# 27_-_PWR_1V375_OPT_3V3_OPT.net
KiCad netlist of a schematic drawn in Altium Designer
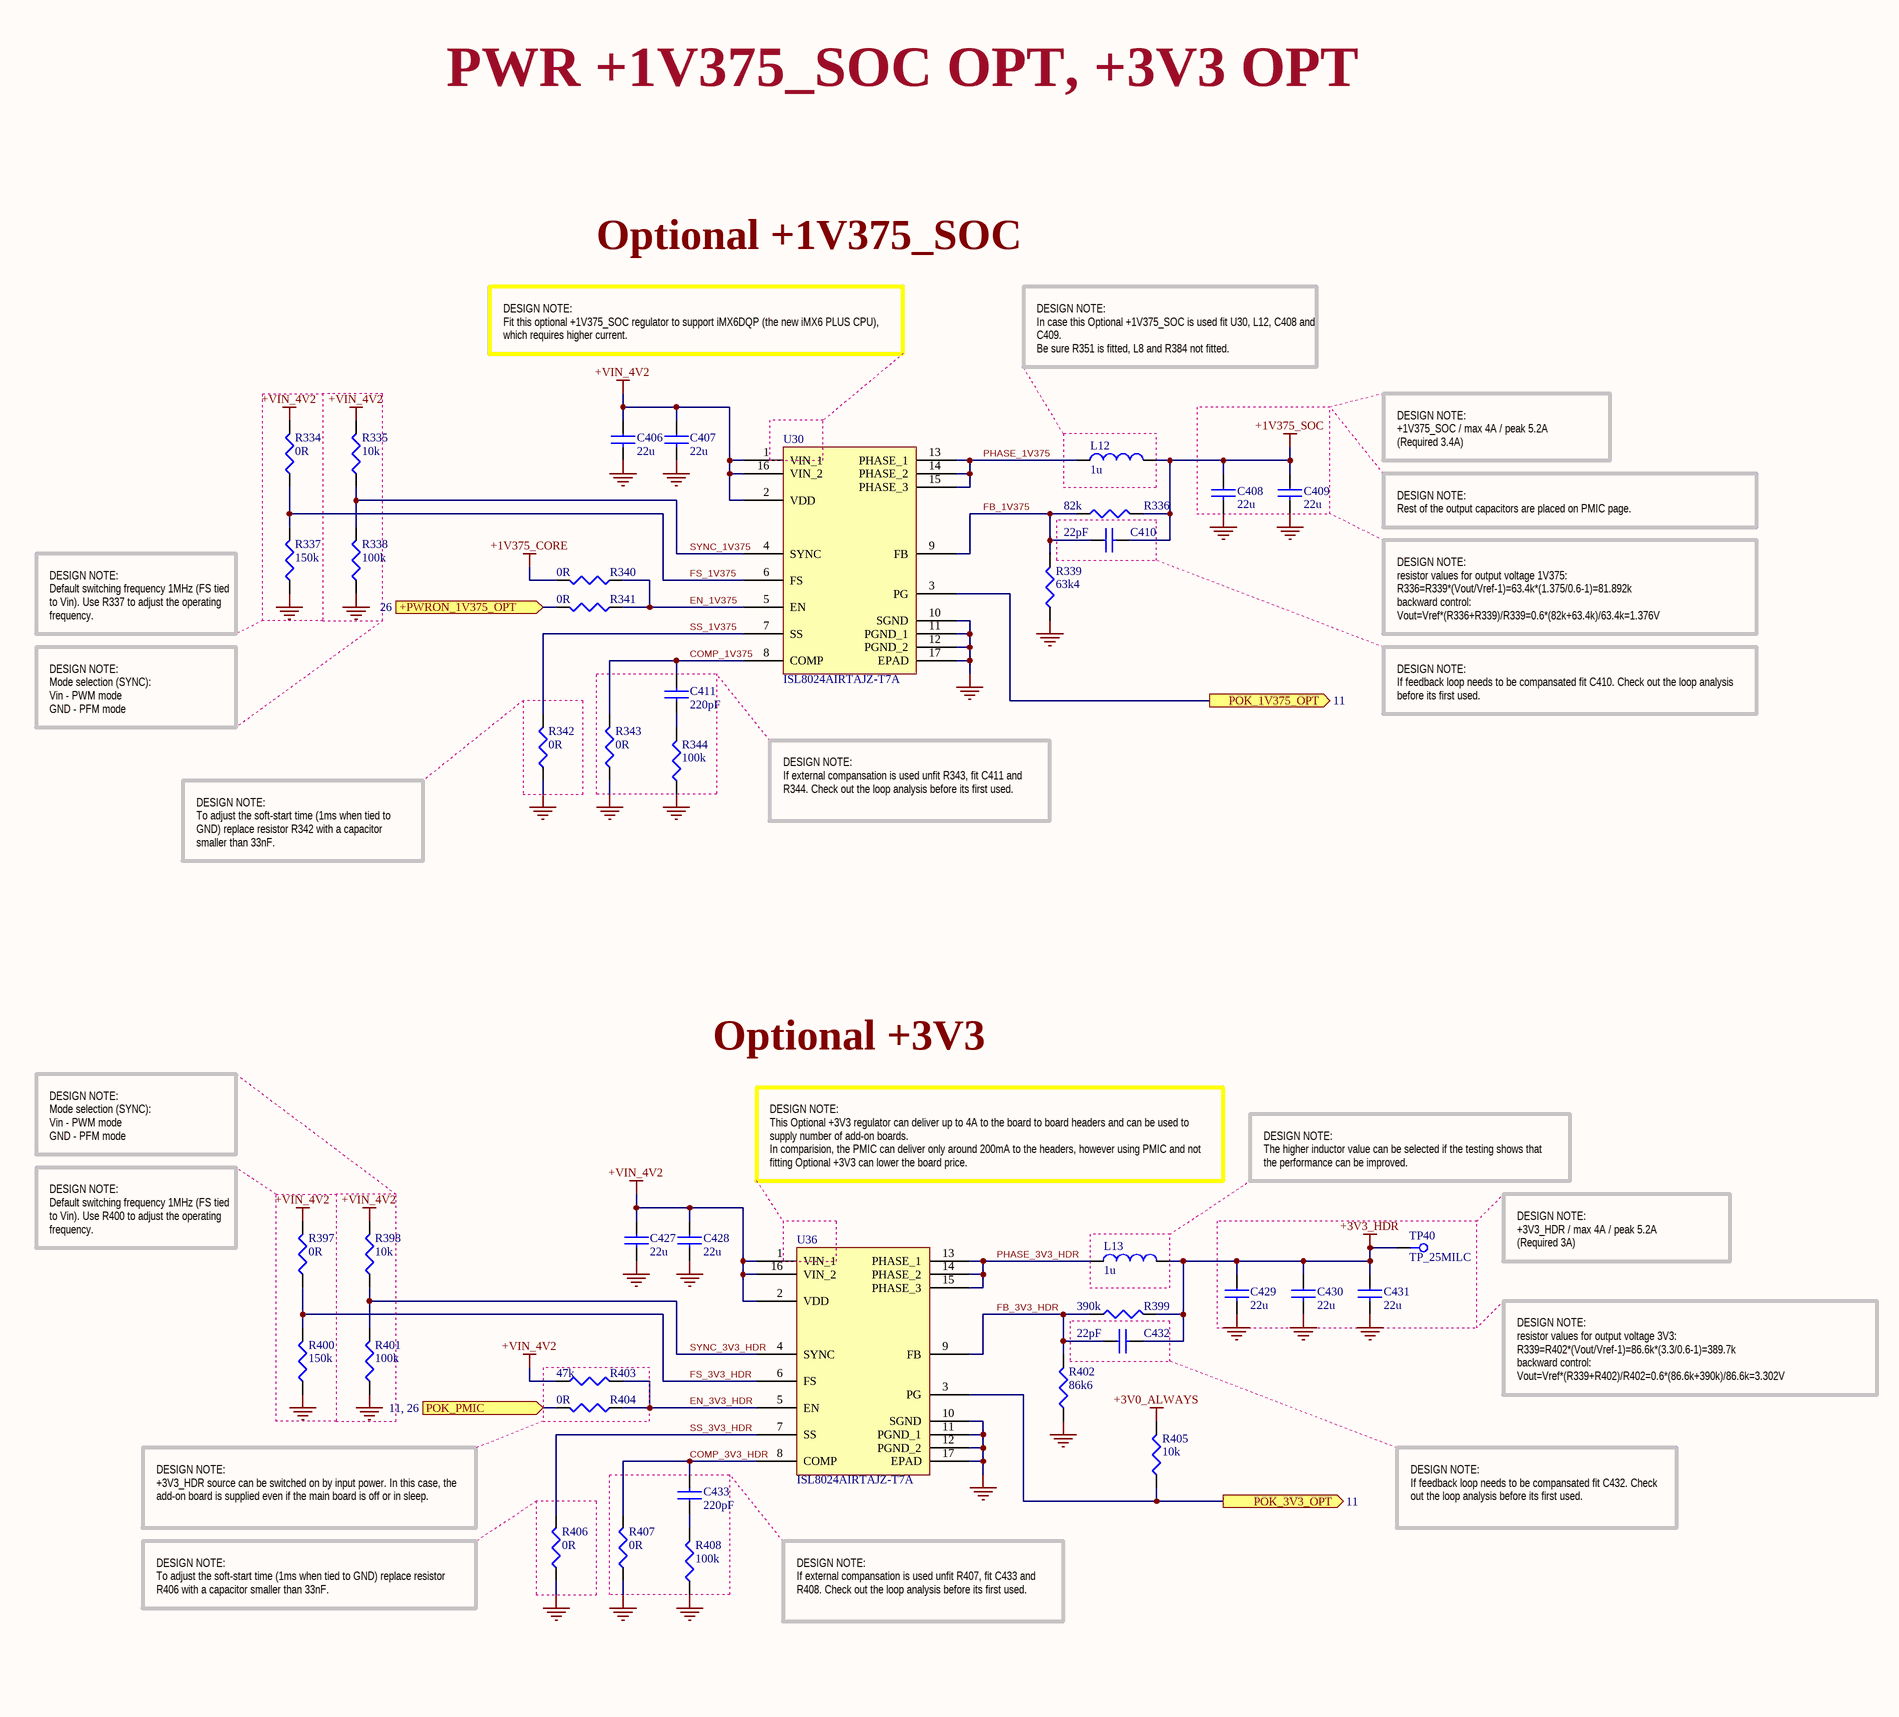
[diagram p0: [27] - PWR 1V375 OPT, 3V3 OPT.SchDoc, left]
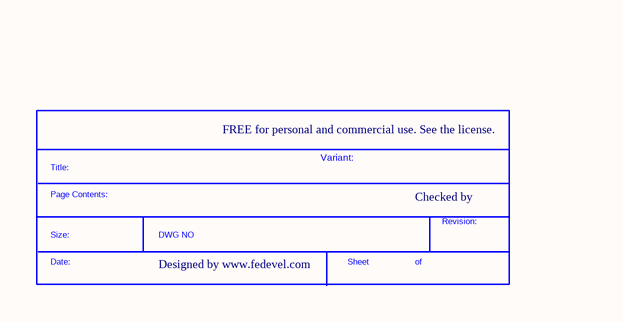
[diagram p1: [27] - PWR 1V375 OPT, 3V3 OPT.SchDoc, right]

(export (version "E")
  (design (tool "Eeschema 10.0.6"))
  (components
    (comp (ref "C406")
      (value "22u")
      (footprint "C0603")
      (description "CAP CER 22UF 6.3V 20% X5R 0603")
      (fields
        (field (name "MANUFACTURER") "TDK Corporation")
        (field (name "MANUFACTURER PART NUMBER") "C1608X5R0J226M080AC")
        (field (name ".CREATOR") "MM")
        (field (name ".CHECKED PCB") "MM")
        (field (name ".CHECKED SCH") "MM")
      )
      (libsource (lib "Integrated_Library_FEDEVEL_APR_2015") (part "C1608X5R0J226M080AC"))
    )
    (comp (ref "C407")
      (value "22u")
      (footprint "C0603")
      (description "CAP CER 22UF 6.3V 20% X5R 0603")
      (fields
        (field (name "MANUFACTURER") "TDK Corporation")
        (field (name "MANUFACTURER PART NUMBER") "C1608X5R0J226M080AC")
        (field (name ".CREATOR") "MM")
        (field (name ".CHECKED PCB") "MM")
        (field (name ".CHECKED SCH") "MM")
      )
      (libsource (lib "Integrated_Library_FEDEVEL_APR_2015") (part "C1608X5R0J226M080AC"))
    )
    (comp (ref "C408")
      (value "22u")
      (footprint "C0603")
      (description "CAP CER 22UF 4V 20% X5R 0603")
      (fields
        (field (name "MANUFACTURER") "Murata Electronics North America")
        (field (name "MANUFACTURER PART NUMBER") "GRM188R60G226MEA0L")
        (field (name ".CREATOR") "MM")
      )
      (libsource (lib "Integrated_Library_FEDEVEL_APR_2015") (part "GRM188R60G226MEA0L"))
    )
    (comp (ref "C409")
      (value "22u")
      (footprint "C0603")
      (description "CAP CER 22UF 4V 20% X5R 0603")
      (fields
        (field (name "MANUFACTURER") "Murata Electronics North America")
        (field (name "MANUFACTURER PART NUMBER") "GRM188R60G226MEA0L")
        (field (name ".CREATOR") "MM")
      )
      (libsource (lib "Integrated_Library_FEDEVEL_APR_2015") (part "GRM188R60G226MEA0L"))
    )
    (comp (ref "C410")
      (value "22pF")
      (footprint "C0402")
      (description "CAP CER 22PF 50V C0G 5% 0402")
      (fields
        (field (name "MANUFACTURER") "TDK Corporation")
        (field (name "MANUFACTURER PART NUMBER") "C1005C0G1H220J")
      )
      (libsource (lib "Integrated_Library_FEDEVEL_APR_2015") (part "C1005C0G1H220J"))
    )
    (comp (ref "C411")
      (value "220pF")
      (footprint "C0402")
      (description "CAP CER 220PF 50V X7R 10% 0402")
      (fields
        (field (name "MANUFACTURER") "TDK Corporation")
        (field (name "MANUFACTURER PART NUMBER") "C1005X7R1H221K")
      )
      (libsource (lib "Integrated_Library_FEDEVEL_APR_2015") (part "C1005X7R1H221K"))
    )
    (comp (ref "C427")
      (value "22u")
      (footprint "C0603")
      (description "CAP CER 22UF 6.3V 20% X5R 0603")
      (fields
        (field (name "MANUFACTURER") "TDK Corporation")
        (field (name "MANUFACTURER PART NUMBER") "C1608X5R0J226M080AC")
        (field (name ".CREATOR") "MM")
        (field (name ".CHECKED PCB") "MM")
        (field (name ".CHECKED SCH") "MM")
      )
      (libsource (lib "Integrated_Library_FEDEVEL_APR_2015") (part "C1608X5R0J226M080AC"))
    )
    (comp (ref "C428")
      (value "22u")
      (footprint "C0603")
      (description "CAP CER 22UF 6.3V 20% X5R 0603")
      (fields
        (field (name "MANUFACTURER") "TDK Corporation")
        (field (name "MANUFACTURER PART NUMBER") "C1608X5R0J226M080AC")
        (field (name ".CREATOR") "MM")
        (field (name ".CHECKED PCB") "MM")
        (field (name ".CHECKED SCH") "MM")
      )
      (libsource (lib "Integrated_Library_FEDEVEL_APR_2015") (part "C1608X5R0J226M080AC"))
    )
    (comp (ref "C429")
      (value "22u")
      (footprint "C0603")
      (description "CAP CER 22UF 4V 20% X5R 0603")
      (fields
        (field (name "MANUFACTURER") "Murata Electronics North America")
        (field (name "MANUFACTURER PART NUMBER") "GRM188R60G226MEA0L")
        (field (name ".CREATOR") "MM")
      )
      (libsource (lib "Integrated_Library_FEDEVEL_APR_2015") (part "GRM188R60G226MEA0L"))
    )
    (comp (ref "C430")
      (value "22u")
      (footprint "C0603")
      (description "CAP CER 22UF 4V 20% X5R 0603")
      (fields
        (field (name "MANUFACTURER") "Murata Electronics North America")
        (field (name "MANUFACTURER PART NUMBER") "GRM188R60G226MEA0L")
        (field (name ".CREATOR") "MM")
      )
      (libsource (lib "Integrated_Library_FEDEVEL_APR_2015") (part "GRM188R60G226MEA0L"))
    )
    (comp (ref "C431")
      (value "22u")
      (footprint "C0603")
      (description "CAP CER 22UF 4V 20% X5R 0603")
      (fields
        (field (name "MANUFACTURER") "Murata Electronics North America")
        (field (name "MANUFACTURER PART NUMBER") "GRM188R60G226MEA0L")
        (field (name ".CREATOR") "MM")
      )
      (libsource (lib "Integrated_Library_FEDEVEL_APR_2015") (part "GRM188R60G226MEA0L"))
    )
    (comp (ref "C432")
      (value "22pF")
      (footprint "C0402")
      (description "CAP CER 22PF 50V C0G 5% 0402")
      (fields
        (field (name "MANUFACTURER") "TDK Corporation")
        (field (name "MANUFACTURER PART NUMBER") "C1005C0G1H220J")
      )
      (libsource (lib "Integrated_Library_FEDEVEL_APR_2015") (part "C1005C0G1H220J"))
    )
    (comp (ref "C433")
      (value "220pF")
      (footprint "C0402")
      (description "CAP CER 220PF 50V X7R 10% 0402")
      (fields
        (field (name "MANUFACTURER") "TDK Corporation")
        (field (name "MANUFACTURER PART NUMBER") "C1005X7R1H221K")
      )
      (libsource (lib "Integrated_Library_FEDEVEL_APR_2015") (part "C1005X7R1H221K"))
    )
    (comp (ref "L12")
      (value "1u")
      (footprint "IHLP_204MILX216MIL")
      (description "INDUCTOR POWER 1.0UH 7.5A SMD")
      (fields
        (field (name "MANUFACTURER") "Vishay Dale")
        (field (name "MANUFACTURER PART NUMBER") "IHLP2020BZER1R0M11")
        (field (name ".CHECKED PCB") "MM")
        (field (name ".CHECKED SCH") "MM")
        (field (name ".CREATOR") "MM")
      )
      (libsource (lib "Integrated_Library_FEDEVEL_APR_2015") (part "IHLP2020BZER1R0M11"))
    )
    (comp (ref "L13")
      (value "1u")
      (footprint "IHLP_204MILX216MIL")
      (description "INDUCTOR POWER 1.0UH 7.5A SMD")
      (fields
        (field (name "MANUFACTURER") "Vishay Dale")
        (field (name "MANUFACTURER PART NUMBER") "IHLP2020BZER1R0M11")
        (field (name ".CHECKED PCB") "MM")
        (field (name ".CHECKED SCH") "MM")
        (field (name ".CREATOR") "MM")
      )
      (libsource (lib "Integrated_Library_FEDEVEL_APR_2015") (part "IHLP2020BZER1R0M11"))
    )
    (comp (ref "R334")
      (value "0R")
      (footprint "R0402")
      (description "RES 0.0 OHM 1/16W 0402 SMD")
      (fields
        (field (name "MANUFACTURER") "Yageo")
        (field (name "MANUFACTURER PART NUMBER") "RC0402JR-070RL")
      )
      (libsource (lib "Integrated_Library_FEDEVEL_APR_2015") (part "RC0402JR-070RL"))
    )
    (comp (ref "R335")
      (value "10k")
      (footprint "R0402")
      (description "RES 10.0K OHM 1/16W 1% 0402 SMD")
      (fields
        (field (name "MANUFACTURER") "Yageo")
        (field (name "MANUFACTURER PART NUMBER") "RC0402FR-0710KL")
      )
      (libsource (lib "Integrated_Library_FEDEVEL_APR_2015") (part "RC0402FR-0710KL"))
    )
    (comp (ref "R336")
      (value "82k")
      (footprint "R0402")
      (description "RES 82.0K OHM 1/16W 1% 0402 SMD")
      (fields
        (field (name "MANUFACTURER") "Yageo")
        (field (name "MANUFACTURER PART NUMBER") "RC0402FR-0782KL")
        (field (name ".CREATOR") "MM")
        (field (name ".CHECKED PCB") "MM")
        (field (name ".CHECKED SCH") "MM")
      )
      (libsource (lib "Integrated_Library_FEDEVEL_APR_2015") (part "RC0402FR-0782KL"))
    )
    (comp (ref "R337")
      (value "150k")
      (footprint "R0402")
      (description "RES 150K OHM 1/16W 1% 0402 SMD")
      (fields
        (field (name "MANUFACTURER") "Yageo")
        (field (name "MANUFACTURER PART NUMBER") "RC0402FR-07150KL")
        (field (name ".CREATOR") "MM")
        (field (name ".CHECKED PCB") "MM")
        (field (name ".CHECKED SCH") "MM")
      )
      (libsource (lib "Integrated_Library_FEDEVEL_APR_2015") (part "RC0402FR-07150KL"))
    )
    (comp (ref "R338")
      (value "100k")
      (footprint "R0402")
      (description "RES 100K OHM 1/16W 1% 0402 SMD")
      (fields
        (field (name "MANUFACTURER") "Stackpole Electronics Inc")
        (field (name "MANUFACTURER PART NUMBER") "RMCF0402FT100K")
      )
      (libsource (lib "Integrated_Library_FEDEVEL_APR_2015") (part "RMCF0402FT100K"))
    )
    (comp (ref "R339")
      (value "63k4")
      (footprint "R0402")
      (description "RES SMD 63.4K OHM 1% 1/16W 0402")
      (fields
        (field (name "MANUFACTURER") "Vishay Dale")
        (field (name "MANUFACTURER PART NUMBER") "CRCW040263K4FKED")
        (field (name ".CHECKED PCB") "MM")
        (field (name ".CHECKED SCH") "MM")
        (field (name ".CREATOR") "MM")
      )
      (libsource (lib "Integrated_Library_FEDEVEL_APR_2015") (part "CRCW040263K4FKED"))
    )
    (comp (ref "R340")
      (value "0R")
      (footprint "R0402")
      (description "RES 0.0 OHM 1/16W 0402 SMD")
      (fields
        (field (name "MANUFACTURER") "Yageo")
        (field (name "MANUFACTURER PART NUMBER") "RC0402JR-070RL")
      )
      (libsource (lib "Integrated_Library_FEDEVEL_APR_2015") (part "RC0402JR-070RL"))
    )
    (comp (ref "R341")
      (value "0R")
      (footprint "R0402")
      (description "RES 0.0 OHM 1/16W 0402 SMD")
      (fields
        (field (name "MANUFACTURER") "Yageo")
        (field (name "MANUFACTURER PART NUMBER") "RC0402JR-070RL")
      )
      (libsource (lib "Integrated_Library_FEDEVEL_APR_2015") (part "RC0402JR-070RL"))
    )
    (comp (ref "R342")
      (value "0R")
      (footprint "R0402")
      (description "RES 0.0 OHM 1/16W 0402 SMD")
      (fields
        (field (name "MANUFACTURER") "Yageo")
        (field (name "MANUFACTURER PART NUMBER") "RC0402JR-070RL")
      )
      (libsource (lib "Integrated_Library_FEDEVEL_APR_2015") (part "RC0402JR-070RL"))
    )
    (comp (ref "R343")
      (value "0R")
      (footprint "R0402")
      (description "RES 0.0 OHM 1/16W 0402 SMD")
      (fields
        (field (name "MANUFACTURER") "Yageo")
        (field (name "MANUFACTURER PART NUMBER") "RC0402JR-070RL")
      )
      (libsource (lib "Integrated_Library_FEDEVEL_APR_2015") (part "RC0402JR-070RL"))
    )
    (comp (ref "R344")
      (value "100k")
      (footprint "R0402")
      (description "RES 100K OHM 1/16W 1% 0402 SMD")
      (fields
        (field (name "MANUFACTURER") "Stackpole Electronics Inc")
        (field (name "MANUFACTURER PART NUMBER") "RMCF0402FT100K")
      )
      (libsource (lib "Integrated_Library_FEDEVEL_APR_2015") (part "RMCF0402FT100K"))
    )
    (comp (ref "R397")
      (value "0R")
      (footprint "R0402")
      (description "RES 0.0 OHM 1/16W 0402 SMD")
      (fields
        (field (name "MANUFACTURER") "Yageo")
        (field (name "MANUFACTURER PART NUMBER") "RC0402JR-070RL")
      )
      (libsource (lib "Integrated_Library_FEDEVEL_APR_2015") (part "RC0402JR-070RL"))
    )
    (comp (ref "R398")
      (value "10k")
      (footprint "R0402")
      (description "RES 10.0K OHM 1/16W 1% 0402 SMD")
      (fields
        (field (name "MANUFACTURER") "Yageo")
        (field (name "MANUFACTURER PART NUMBER") "RC0402FR-0710KL")
      )
      (libsource (lib "Integrated_Library_FEDEVEL_APR_2015") (part "RC0402FR-0710KL"))
    )
    (comp (ref "R399")
      (value "390k")
      (footprint "R0402")
      (description "RES 390K OHM 1/16W 1% 0402 SMD")
      (fields
        (field (name "MANUFACTURER") "Vishay Dale")
        (field (name "MANUFACTURER PART NUMBER") "CRCW0402390KFKED")
        (field (name ".CREATOR") "MM")
      )
      (libsource (lib "Integrated_Library_FEDEVEL_APR_2015") (part "CRCW0402390KFKED"))
    )
    (comp (ref "R400")
      (value "150k")
      (footprint "R0402")
      (description "RES 150K OHM 1/16W 1% 0402 SMD")
      (fields
        (field (name "MANUFACTURER") "Yageo")
        (field (name "MANUFACTURER PART NUMBER") "RC0402FR-07150KL")
        (field (name ".CREATOR") "MM")
        (field (name ".CHECKED PCB") "MM")
        (field (name ".CHECKED SCH") "MM")
      )
      (libsource (lib "Integrated_Library_FEDEVEL_APR_2015") (part "RC0402FR-07150KL"))
    )
    (comp (ref "R401")
      (value "100k")
      (footprint "R0402")
      (description "RES 100K OHM 1/16W 1% 0402 SMD")
      (fields
        (field (name "MANUFACTURER") "Stackpole Electronics Inc")
        (field (name "MANUFACTURER PART NUMBER") "RMCF0402FT100K")
      )
      (libsource (lib "Integrated_Library_FEDEVEL_APR_2015") (part "RMCF0402FT100K"))
    )
    (comp (ref "R402")
      (value "86k6")
      (footprint "R0402")
      (description "RES SMD 86.6K OHM 1% 1/16W 0402")
      (fields
        (field (name "MANUFACTURER") "Yageo")
        (field (name "MANUFACTURER PART NUMBER") "RC0402FR-0786K6L")
        (field (name ".CREATOR") "MM")
        (field (name ".CHECKED PCB") "MM")
        (field (name ".CHECKED SCH") "MM")
      )
      (libsource (lib "Integrated_Library_FEDEVEL_APR_2015") (part "RC0402FR-0786K6L"))
    )
    (comp (ref "R403")
      (value "47k")
      (footprint "R0402")
      (description "RES 47.0K OHM 1/16W 1% 0402 SMD")
      (fields
        (field (name "MANUFACTURER") "Yageo")
        (field (name "MANUFACTURER PART NUMBER") "RC0402FR-0747KL")
      )
      (libsource (lib "Integrated_Library_FEDEVEL_APR_2015") (part "RC0402FR-0747KL"))
    )
    (comp (ref "R404")
      (value "0R")
      (footprint "R0402")
      (description "RES 0.0 OHM 1/16W 0402 SMD")
      (fields
        (field (name "MANUFACTURER") "Yageo")
        (field (name "MANUFACTURER PART NUMBER") "RC0402JR-070RL")
      )
      (libsource (lib "Integrated_Library_FEDEVEL_APR_2015") (part "RC0402JR-070RL"))
    )
    (comp (ref "R405")
      (value "10k")
      (footprint "R0402")
      (description "RES 10.0K OHM 1/16W 1% 0402 SMD")
      (fields
        (field (name "MANUFACTURER") "Yageo")
        (field (name "MANUFACTURER PART NUMBER") "RC0402FR-0710KL")
      )
      (libsource (lib "Integrated_Library_FEDEVEL_APR_2015") (part "RC0402FR-0710KL"))
    )
    (comp (ref "R406")
      (value "0R")
      (footprint "R0402")
      (description "RES 0.0 OHM 1/16W 0402 SMD")
      (fields
        (field (name "MANUFACTURER") "Yageo")
        (field (name "MANUFACTURER PART NUMBER") "RC0402JR-070RL")
      )
      (libsource (lib "Integrated_Library_FEDEVEL_APR_2015") (part "RC0402JR-070RL"))
    )
    (comp (ref "R407")
      (value "0R")
      (footprint "R0402")
      (description "RES 0.0 OHM 1/16W 0402 SMD")
      (fields
        (field (name "MANUFACTURER") "Yageo")
        (field (name "MANUFACTURER PART NUMBER") "RC0402JR-070RL")
      )
      (libsource (lib "Integrated_Library_FEDEVEL_APR_2015") (part "RC0402JR-070RL"))
    )
    (comp (ref "R408")
      (value "100k")
      (footprint "R0402")
      (description "RES 100K OHM 1/16W 1% 0402 SMD")
      (fields
        (field (name "MANUFACTURER") "Stackpole Electronics Inc")
        (field (name "MANUFACTURER PART NUMBER") "RMCF0402FT100K")
      )
      (libsource (lib "Integrated_Library_FEDEVEL_APR_2015") (part "RMCF0402FT100K"))
    )
    (comp (ref "TP40")
      (value "TP_25MILC")
      (footprint "TP_25C")
      (description "Test Point 25mil")
      (libsource (lib "Integrated_Library_FEDEVEL_APR_2015") (part "TP_25MILC"))
    )
    (comp (ref "U30")
      (value "ISL8024AIRTAJZ-T7A")
      (footprint "16-TQFN_3mmx3mm_V1.1")
      (description "IC REG BUCK SYNC ADJ 4A 16TQFN")
      (fields
        (field (name "MANUFACTURER") "Intersil")
        (field (name ".CREATOR") "MM")
        (field (name ".CHECKED PCB") "MM")
        (field (name ".CHECKED SCH") "MM")
      )
      (libsource (lib "Integrated_Library_FEDEVEL_APR_2015") (part "ISL8024AIRTAJZ-T7A"))
    )
    (comp (ref "U36")
      (value "ISL8024AIRTAJZ-T7A")
      (footprint "16-TQFN_3mmx3mm_V1.1")
      (description "IC REG BUCK SYNC ADJ 4A 16TQFN")
      (fields
        (field (name "MANUFACTURER") "Intersil")
        (field (name ".CREATOR") "MM")
        (field (name ".CHECKED PCB") "MM")
        (field (name ".CHECKED SCH") "MM")
      )
      (libsource (lib "Integrated_Library_FEDEVEL_APR_2015") (part "ISL8024AIRTAJZ-T7A"))
    )
  )
  (nets
    (net (code "1") (name "+1V375_CORE") (class "Default")
      (node (ref "R340") (pin "2") (pinfunction "2_2") (pintype "passive"))
    )
    (net (code "2") (name "+1V375_SOC") (class "Default")
      (node (ref "C408") (pin "1") (pinfunction "1_1") (pintype "passive"))
      (node (ref "C409") (pin "1") (pinfunction "1_1") (pintype "passive"))
      (node (ref "C410") (pin "2") (pinfunction "2_2") (pintype "passive"))
      (node (ref "L12") (pin "2") (pinfunction "2_2") (pintype "passive"))
      (node (ref "R336") (pin "2") (pinfunction "2_2") (pintype "passive"))
    )
    (net (code "3") (name "+3V0_ALWAYS") (class "Default")
      (node (ref "R405") (pin "2") (pinfunction "2_2") (pintype "passive"))
    )
    (net (code "4") (name "+3V3_HDR") (class "Default")
      (node (ref "C429") (pin "1") (pinfunction "1_1") (pintype "passive"))
      (node (ref "C430") (pin "1") (pinfunction "1_1") (pintype "passive"))
      (node (ref "C431") (pin "1") (pinfunction "1_1") (pintype "passive"))
      (node (ref "C432") (pin "2") (pinfunction "2_2") (pintype "passive"))
      (node (ref "L13") (pin "2") (pinfunction "2_2") (pintype "passive"))
      (node (ref "R399") (pin "2") (pinfunction "2_2") (pintype "passive"))
      (node (ref "TP40") (pin "1") (pinfunction "1_1") (pintype "passive"))
    )
    (net (code "5") (name "+VIN_4V2") (class "Default")
      (node (ref "C406") (pin "1") (pinfunction "1_1") (pintype "passive"))
      (node (ref "C407") (pin "1") (pinfunction "1_1") (pintype "passive"))
      (node (ref "C427") (pin "1") (pinfunction "1_1") (pintype "passive"))
      (node (ref "C428") (pin "1") (pinfunction "1_1") (pintype "passive"))
      (node (ref "R334") (pin "2") (pinfunction "2_2") (pintype "passive"))
      (node (ref "R335") (pin "2") (pinfunction "2_2") (pintype "passive"))
      (node (ref "R397") (pin "2") (pinfunction "2_2") (pintype "passive"))
      (node (ref "R398") (pin "2") (pinfunction "2_2") (pintype "passive"))
      (node (ref "R403") (pin "1") (pinfunction "1_1") (pintype "passive"))
      (node (ref "U30") (pin "1") (pinfunction "VIN_1_1") (pintype "passive"))
      (node (ref "U30") (pin "16") (pinfunction "VIN_2_16") (pintype "passive"))
      (node (ref "U30") (pin "2") (pinfunction "VDD_2") (pintype "passive"))
      (node (ref "U36") (pin "1") (pinfunction "VIN_1_1") (pintype "passive"))
      (node (ref "U36") (pin "16") (pinfunction "VIN_2_16") (pintype "passive"))
      (node (ref "U36") (pin "2") (pinfunction "VDD_2") (pintype "passive"))
    )
    (net (code "6") (name "/+PWRON_1V375_OPT") (class "Default")
      (node (ref "R341") (pin "2") (pinfunction "2_2") (pintype "passive"))
    )
    (net (code "7") (name "/COMP_1V375") (class "Default")
      (node (ref "C411") (pin "2") (pinfunction "2_2") (pintype "passive"))
      (node (ref "R343") (pin "2") (pinfunction "2_2") (pintype "passive"))
      (node (ref "U30") (pin "8") (pinfunction "COMP_8") (pintype "passive"))
    )
    (net (code "8") (name "/COMP_3V3_HDR") (class "Default")
      (node (ref "C433") (pin "2") (pinfunction "2_2") (pintype "passive"))
      (node (ref "R407") (pin "2") (pinfunction "2_2") (pintype "passive"))
      (node (ref "U36") (pin "8") (pinfunction "COMP_8") (pintype "passive"))
    )
    (net (code "9") (name "/EN_1V375") (class "Default")
      (node (ref "R340") (pin "1") (pinfunction "1_1") (pintype "passive"))
      (node (ref "R341") (pin "1") (pinfunction "1_1") (pintype "passive"))
      (node (ref "U30") (pin "5") (pinfunction "EN_5") (pintype "passive"))
    )
    (net (code "10") (name "/EN_3V3_HDR") (class "Default")
      (node (ref "R403") (pin "2") (pinfunction "2_2") (pintype "passive"))
      (node (ref "R404") (pin "1") (pinfunction "1_1") (pintype "passive"))
      (node (ref "U36") (pin "5") (pinfunction "EN_5") (pintype "passive"))
    )
    (net (code "11") (name "/FB_1V375") (class "Default")
      (node (ref "C410") (pin "1") (pinfunction "1_1") (pintype "passive"))
      (node (ref "R336") (pin "1") (pinfunction "1_1") (pintype "passive"))
      (node (ref "R339") (pin "2") (pinfunction "2_2") (pintype "passive"))
      (node (ref "U30") (pin "9") (pinfunction "FB_9") (pintype "passive"))
    )
    (net (code "12") (name "/FB_3V3_HDR") (class "Default")
      (node (ref "C432") (pin "1") (pinfunction "1_1") (pintype "passive"))
      (node (ref "R399") (pin "1") (pinfunction "1_1") (pintype "passive"))
      (node (ref "R402") (pin "2") (pinfunction "2_2") (pintype "passive"))
      (node (ref "U36") (pin "9") (pinfunction "FB_9") (pintype "passive"))
    )
    (net (code "13") (name "/FS_1V375") (class "Default")
      (node (ref "R334") (pin "1") (pinfunction "1_1") (pintype "passive"))
      (node (ref "R337") (pin "2") (pinfunction "2_2") (pintype "passive"))
      (node (ref "U30") (pin "6") (pinfunction "FS_6") (pintype "passive"))
    )
    (net (code "14") (name "/FS_3V3_HDR") (class "Default")
      (node (ref "R397") (pin "1") (pinfunction "1_1") (pintype "passive"))
      (node (ref "R400") (pin "2") (pinfunction "2_2") (pintype "passive"))
      (node (ref "U36") (pin "6") (pinfunction "FS_6") (pintype "passive"))
    )
    (net (code "15") (name "/PHASE_1V375") (class "Default")
      (node (ref "L12") (pin "1") (pinfunction "1_1") (pintype "passive"))
      (node (ref "U30") (pin "13") (pinfunction "PHASE_1_13") (pintype "passive"))
      (node (ref "U30") (pin "14") (pinfunction "PHASE_2_14") (pintype "passive"))
      (node (ref "U30") (pin "15") (pinfunction "PHASE_3_15") (pintype "passive"))
    )
    (net (code "16") (name "/PHASE_3V3_HDR") (class "Default")
      (node (ref "L13") (pin "1") (pinfunction "1_1") (pintype "passive"))
      (node (ref "U36") (pin "13") (pinfunction "PHASE_1_13") (pintype "passive"))
      (node (ref "U36") (pin "14") (pinfunction "PHASE_2_14") (pintype "passive"))
      (node (ref "U36") (pin "15") (pinfunction "PHASE_3_15") (pintype "passive"))
    )
    (net (code "17") (name "/POK_1V375_OPT") (class "Default")
      (node (ref "U30") (pin "3") (pinfunction "PG_3") (pintype "passive"))
    )
    (net (code "18") (name "/POK_3V3_OPT") (class "Default")
      (node (ref "R405") (pin "1") (pinfunction "1_1") (pintype "passive"))
      (node (ref "U36") (pin "3") (pinfunction "PG_3") (pintype "passive"))
    )
    (net (code "19") (name "/POK_PMIC") (class "Default")
      (node (ref "R404") (pin "2") (pinfunction "2_2") (pintype "passive"))
    )
    (net (code "20") (name "/SS_1V375") (class "Default")
      (node (ref "R342") (pin "2") (pinfunction "2_2") (pintype "passive"))
      (node (ref "U30") (pin "7") (pinfunction "SS_7") (pintype "passive"))
    )
    (net (code "21") (name "/SS_3V3_HDR") (class "Default")
      (node (ref "R406") (pin "2") (pinfunction "2_2") (pintype "passive"))
      (node (ref "U36") (pin "7") (pinfunction "SS_7") (pintype "passive"))
    )
    (net (code "22") (name "/SYNC_1V375") (class "Default")
      (node (ref "R335") (pin "1") (pinfunction "1_1") (pintype "passive"))
      (node (ref "R338") (pin "2") (pinfunction "2_2") (pintype "passive"))
      (node (ref "U30") (pin "4") (pinfunction "SYNC_4") (pintype "passive"))
    )
    (net (code "23") (name "/SYNC_3V3_HDR") (class "Default")
      (node (ref "R398") (pin "1") (pinfunction "1_1") (pintype "passive"))
      (node (ref "R401") (pin "2") (pinfunction "2_2") (pintype "passive"))
      (node (ref "U36") (pin "4") (pinfunction "SYNC_4") (pintype "passive"))
    )
    (net (code "24") (name "GND") (class "Default")
      (node (ref "C406") (pin "2") (pinfunction "2_2") (pintype "passive"))
      (node (ref "C407") (pin "2") (pinfunction "2_2") (pintype "passive"))
      (node (ref "C408") (pin "2") (pinfunction "2_2") (pintype "passive"))
      (node (ref "C409") (pin "2") (pinfunction "2_2") (pintype "passive"))
      (node (ref "C427") (pin "2") (pinfunction "2_2") (pintype "passive"))
      (node (ref "C428") (pin "2") (pinfunction "2_2") (pintype "passive"))
      (node (ref "C429") (pin "2") (pinfunction "2_2") (pintype "passive"))
      (node (ref "C430") (pin "2") (pinfunction "2_2") (pintype "passive"))
      (node (ref "C431") (pin "2") (pinfunction "2_2") (pintype "passive"))
      (node (ref "R337") (pin "1") (pinfunction "1_1") (pintype "passive"))
      (node (ref "R338") (pin "1") (pinfunction "1_1") (pintype "passive"))
      (node (ref "R339") (pin "1") (pinfunction "1_1") (pintype "passive"))
      (node (ref "R342") (pin "1") (pinfunction "1_1") (pintype "passive"))
      (node (ref "R343") (pin "1") (pinfunction "1_1") (pintype "passive"))
      (node (ref "R344") (pin "1") (pinfunction "1_1") (pintype "passive"))
      (node (ref "R400") (pin "1") (pinfunction "1_1") (pintype "passive"))
      (node (ref "R401") (pin "1") (pinfunction "1_1") (pintype "passive"))
      (node (ref "R402") (pin "1") (pinfunction "1_1") (pintype "passive"))
      (node (ref "R406") (pin "1") (pinfunction "1_1") (pintype "passive"))
      (node (ref "R407") (pin "1") (pinfunction "1_1") (pintype "passive"))
      (node (ref "R408") (pin "1") (pinfunction "1_1") (pintype "passive"))
      (node (ref "U30") (pin "10") (pinfunction "SGND_10") (pintype "passive"))
      (node (ref "U30") (pin "11") (pinfunction "PGND_1_11") (pintype "passive"))
      (node (ref "U30") (pin "12") (pinfunction "PGND_2_12") (pintype "passive"))
      (node (ref "U30") (pin "17") (pinfunction "EPAD_17") (pintype "passive"))
      (node (ref "U36") (pin "10") (pinfunction "SGND_10") (pintype "passive"))
      (node (ref "U36") (pin "11") (pinfunction "PGND_1_11") (pintype "passive"))
      (node (ref "U36") (pin "12") (pinfunction "PGND_2_12") (pintype "passive"))
      (node (ref "U36") (pin "17") (pinfunction "EPAD_17") (pintype "passive"))
    )
    (net (code "25") (name "Net-(C411-Pad1)") (class "Default")
      (node (ref "C411") (pin "1") (pinfunction "1_1") (pintype "passive"))
      (node (ref "R344") (pin "2") (pinfunction "2_2") (pintype "passive"))
    )
    (net (code "26") (name "Net-(C433-Pad1)") (class "Default")
      (node (ref "C433") (pin "1") (pinfunction "1_1") (pintype "passive"))
      (node (ref "R408") (pin "2") (pinfunction "2_2") (pintype "passive"))
    )
  )
)
